# lhs.net
KiCad netlist of a schematic drawn in EAGLE
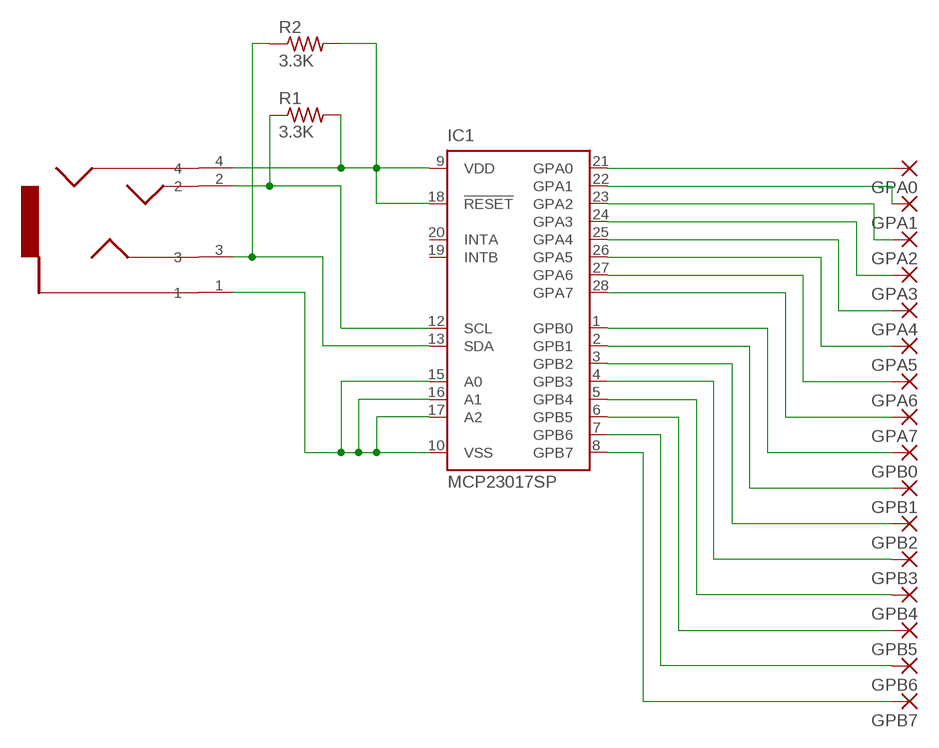
[diagram p0: schematic, sheet 1]

(export (version "E")
  (design (tool "Eeschema 10.0.6"))
  (components
    (comp (ref "GPA0")
      (value "1,6/0,8")
      (footprint "eagle-import:1,6_0,8")
      (libsource (lib "eagle-import") (part "1,6/0,8"))
    )
    (comp (ref "GPA1")
      (value "1,6/0,8")
      (footprint "eagle-import:1,6_0,8")
      (libsource (lib "eagle-import") (part "1,6/0,8"))
    )
    (comp (ref "GPA2")
      (value "1,6/0,8")
      (footprint "eagle-import:1,6_0,8")
      (libsource (lib "eagle-import") (part "1,6/0,8"))
    )
    (comp (ref "GPA3")
      (value "1,6/0,8")
      (footprint "eagle-import:1,6_0,8")
      (libsource (lib "eagle-import") (part "1,6/0,8"))
    )
    (comp (ref "GPA4")
      (value "1,6/0,8")
      (footprint "eagle-import:1,6_0,8")
      (libsource (lib "eagle-import") (part "1,6/0,8"))
    )
    (comp (ref "GPA5")
      (value "1,6/0,8")
      (footprint "eagle-import:1,6_0,8")
      (libsource (lib "eagle-import") (part "1,6/0,8"))
    )
    (comp (ref "GPA6")
      (value "1,6/0,8")
      (footprint "eagle-import:1,6_0,8")
      (libsource (lib "eagle-import") (part "1,6/0,8"))
    )
    (comp (ref "GPA7")
      (value "1,6/0,8")
      (footprint "eagle-import:1,6_0,8")
      (libsource (lib "eagle-import") (part "1,6/0,8"))
    )
    (comp (ref "GPB0")
      (value "1,6/0,8")
      (footprint "eagle-import:1,6_0,8")
      (libsource (lib "eagle-import") (part "1,6/0,8"))
    )
    (comp (ref "GPB1")
      (value "1,6/0,8")
      (footprint "eagle-import:1,6_0,8")
      (libsource (lib "eagle-import") (part "1,6/0,8"))
    )
    (comp (ref "GPB2")
      (value "1,6/0,8")
      (footprint "eagle-import:1,6_0,8")
      (libsource (lib "eagle-import") (part "1,6/0,8"))
    )
    (comp (ref "GPB3")
      (value "1,6/0,8")
      (footprint "eagle-import:1,6_0,8")
      (libsource (lib "eagle-import") (part "1,6/0,8"))
    )
    (comp (ref "GPB4")
      (value "1,6/0,8")
      (footprint "eagle-import:1,6_0,8")
      (libsource (lib "eagle-import") (part "1,6/0,8"))
    )
    (comp (ref "GPB5")
      (value "1,6/0,8")
      (footprint "eagle-import:1,6_0,8")
      (libsource (lib "eagle-import") (part "1,6/0,8"))
    )
    (comp (ref "GPB6")
      (value "1,6/0,8")
      (footprint "eagle-import:1,6_0,8")
      (libsource (lib "eagle-import") (part "1,6/0,8"))
    )
    (comp (ref "GPB7")
      (value "1,6/0,8")
      (footprint "eagle-import:1,6_0,8")
      (libsource (lib "eagle-import") (part "1,6/0,8"))
    )
    (comp (ref "IC1")
      (value "MCP23017SP")
      (footprint "eagle-import:DIL28-3")
      (fields (field (name "MF") "MICROCHIP") (field (name "MPN") "MCP23017-E/SP"))
      (libsource (lib "eagle-import") (part "MCP23017SP"))
    )
    (comp (ref "R1")
      (value "3.3K")
      (footprint "eagle-import:0207_10")
      (libsource (lib "eagle-import") (part "R-US_0207/10"))
    )
    (comp (ref "R2")
      (value "3.3K")
      (footprint "eagle-import:0207_10")
      (libsource (lib "eagle-import") (part "R-US_0207/10"))
    )
    (comp (ref "U$1")
      (value "SJ-43514_HEADPHONES_3.5MM_X4")
      (footprint "eagle-import:SJ-43514_HEADPHONES-3.5MM_X4")
      (libsource (lib "eagle-import") (part "SJ-43514_HEADPHONES_3.5MM_X4"))
    )
  )
  (nets
    (net (code "1") (name "Net-(GPA0-P)") (class "Default")
      (node (ref "GPA0") (pin "1") (pinfunction "P_1") (pintype "passive"))
      (node (ref "IC1") (pin "21") (pinfunction "GPA0_21") (pintype "bidirectional"))
    )
    (net (code "2") (name "Net-(GPA1-P)") (class "Default")
      (node (ref "GPA1") (pin "1") (pinfunction "P_1") (pintype "passive"))
      (node (ref "IC1") (pin "22") (pinfunction "GPA1_22") (pintype "bidirectional"))
    )
    (net (code "3") (name "Net-(GPA2-P)") (class "Default")
      (node (ref "GPA2") (pin "1") (pinfunction "P_1") (pintype "passive"))
      (node (ref "IC1") (pin "23") (pinfunction "GPA2_23") (pintype "bidirectional"))
    )
    (net (code "4") (name "Net-(GPA3-P)") (class "Default")
      (node (ref "GPA3") (pin "1") (pinfunction "P_1") (pintype "passive"))
      (node (ref "IC1") (pin "24") (pinfunction "GPA3_24") (pintype "bidirectional"))
    )
    (net (code "5") (name "Net-(GPA4-P)") (class "Default")
      (node (ref "GPA4") (pin "1") (pinfunction "P_1") (pintype "passive"))
      (node (ref "IC1") (pin "25") (pinfunction "GPA4_25") (pintype "bidirectional"))
    )
    (net (code "6") (name "Net-(GPA5-P)") (class "Default")
      (node (ref "GPA5") (pin "1") (pinfunction "P_1") (pintype "passive"))
      (node (ref "IC1") (pin "26") (pinfunction "GPA5_26") (pintype "bidirectional"))
    )
    (net (code "7") (name "Net-(GPA6-P)") (class "Default")
      (node (ref "GPA6") (pin "1") (pinfunction "P_1") (pintype "passive"))
      (node (ref "IC1") (pin "27") (pinfunction "GPA6_27") (pintype "bidirectional"))
    )
    (net (code "8") (name "Net-(GPA7-P)") (class "Default")
      (node (ref "GPA7") (pin "1") (pinfunction "P_1") (pintype "passive"))
      (node (ref "IC1") (pin "28") (pinfunction "GPA7_28") (pintype "bidirectional"))
    )
    (net (code "9") (name "Net-(GPB0-P)") (class "Default")
      (node (ref "GPB0") (pin "1") (pinfunction "P_1") (pintype "passive"))
      (node (ref "IC1") (pin "1") (pinfunction "GPB0_1") (pintype "bidirectional"))
    )
    (net (code "10") (name "Net-(GPB1-P)") (class "Default")
      (node (ref "GPB1") (pin "1") (pinfunction "P_1") (pintype "passive"))
      (node (ref "IC1") (pin "2") (pinfunction "GPB1_2") (pintype "bidirectional"))
    )
    (net (code "11") (name "Net-(GPB2-P)") (class "Default")
      (node (ref "GPB2") (pin "1") (pinfunction "P_1") (pintype "passive"))
      (node (ref "IC1") (pin "3") (pinfunction "GPB2_3") (pintype "bidirectional"))
    )
    (net (code "12") (name "Net-(GPB3-P)") (class "Default")
      (node (ref "GPB3") (pin "1") (pinfunction "P_1") (pintype "passive"))
      (node (ref "IC1") (pin "4") (pinfunction "GPB3_4") (pintype "bidirectional"))
    )
    (net (code "13") (name "Net-(GPB4-P)") (class "Default")
      (node (ref "GPB4") (pin "1") (pinfunction "P_1") (pintype "passive"))
      (node (ref "IC1") (pin "5") (pinfunction "GPB4_5") (pintype "bidirectional"))
    )
    (net (code "14") (name "Net-(GPB5-P)") (class "Default")
      (node (ref "GPB5") (pin "1") (pinfunction "P_1") (pintype "passive"))
      (node (ref "IC1") (pin "6") (pinfunction "GPB5_6") (pintype "bidirectional"))
    )
    (net (code "15") (name "Net-(GPB6-P)") (class "Default")
      (node (ref "GPB6") (pin "1") (pinfunction "P_1") (pintype "passive"))
      (node (ref "IC1") (pin "7") (pinfunction "GPB6_7") (pintype "bidirectional"))
    )
    (net (code "16") (name "Net-(GPB7-P)") (class "Default")
      (node (ref "GPB7") (pin "1") (pinfunction "P_1") (pintype "passive"))
      (node (ref "IC1") (pin "8") (pinfunction "GPB7_8") (pintype "bidirectional"))
    )
    (net (code "17") (name "Net-(IC1-A0)") (class "Default")
      (node (ref "IC1") (pin "10") (pinfunction "VSS_10") (pintype "power_in"))
      (node (ref "IC1") (pin "15") (pinfunction "A0_15") (pintype "input"))
      (node (ref "IC1") (pin "16") (pinfunction "A1_16") (pintype "input"))
      (node (ref "IC1") (pin "17") (pinfunction "A2_17") (pintype "input"))
      (node (ref "U$1") (pin "1") (pinfunction "1_1") (pintype "bidirectional"))
    )
    (net (code "18") (name "Net-(IC1-SCL)") (class "Default")
      (node (ref "IC1") (pin "12") (pinfunction "SCL_12") (pintype "input"))
      (node (ref "R1") (pin "1") (pinfunction "1_1") (pintype "passive"))
      (node (ref "U$1") (pin "2") (pinfunction "2_2") (pintype "bidirectional"))
    )
    (net (code "19") (name "Net-(IC1-SDA)") (class "Default")
      (node (ref "IC1") (pin "13") (pinfunction "SDA_13") (pintype "bidirectional"))
      (node (ref "R2") (pin "1") (pinfunction "1_1") (pintype "passive"))
      (node (ref "U$1") (pin "3") (pinfunction "3_3") (pintype "bidirectional"))
    )
    (net (code "20") (name "Net-(IC1-VDD)") (class "Default")
      (node (ref "IC1") (pin "18") (pinfunction "~{RESET}_18") (pintype "input"))
      (node (ref "IC1") (pin "9") (pinfunction "VDD_9") (pintype "power_in"))
      (node (ref "R1") (pin "2") (pinfunction "2_2") (pintype "passive"))
      (node (ref "R2") (pin "2") (pinfunction "2_2") (pintype "passive"))
      (node (ref "U$1") (pin "4") (pinfunction "4_4") (pintype "bidirectional"))
    )
    (net (code "21") (name "unconnected-(IC1-INTA-Pad20)") (class "Default")
      (node (ref "IC1") (pin "20") (pinfunction "INTA_20") (pintype "output"))
    )
    (net (code "22") (name "unconnected-(IC1-INTB-Pad19)") (class "Default")
      (node (ref "IC1") (pin "19") (pinfunction "INTB_19") (pintype "output"))
    )
  )
)
